# BLE_breakout.net
KiCad netlist of a schematic drawn in Altium Designer
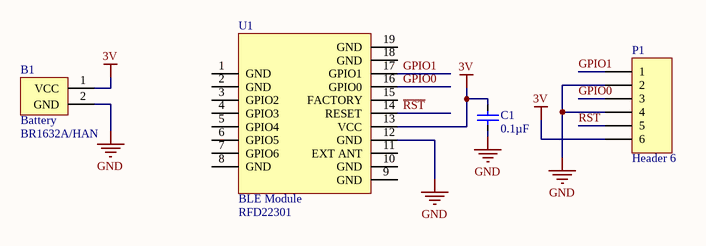
[diagram p0: BLE_breakout.SchDoc]

(export (version "E")
  (design (tool "Eeschema 10.0.6"))
  (components
    (comp (ref "B1")
      (value "Battery")
      (footprint "Battery_type1")
      (fields
        (field (name "MANUFACTURER") "Panasonic")
        (field (name "MANUFACTURER PART NUMBER") "BR1632A/HAN")
      )
      (libsource (lib "BLE_breakout") (part "Battery"))
    )
    (comp (ref "C1")
      (value "Cap 0.1µF")
      (footprint "CAPC1608N")
      (description "CAP CER 0.1UF 16V X7R 0603")
      (fields
        (field (name "MANUFACTURER") "Yageo")
        (field (name "MANUFACTURER PART NUMBER") "CC0603KRX7R7BB104")
        (field (name "CAPACITANCE") "0.1µF")
      )
      (libsource (lib "Formula_Library") (part "Cap 0.1µF"))
    )
    (comp (ref "P1")
      (value "Header 6")
      (footprint "HDR1X6")
      (description "Header, 6-Pin")
      (fields (field (name "PUBLISHER") "Altium Limited"))
      (libsource (lib "Miscellaneous Connectors") (part "Header 6"))
    )
    (comp (ref "U1")
      (value "BLE Module")
      (footprint "BLE_module")
      (fields (field (name "MANUFACTURER") "RF Digital") (field (name "MANUFACTURER PART NUMBER") "RFD22301"))
      (libsource (lib "BLE_breakout") (part "BLE Module"))
    )
  )
  (nets
    (net (code "1") (name "/GPIO0") (class "Default")
      (node (ref "P1") (pin "3") (pinfunction "3_3") (pintype "passive"))
      (node (ref "U1") (pin "16") (pinfunction "GPIO0_16") (pintype "passive"))
    )
    (net (code "2") (name "/GPIO1") (class "Default")
      (node (ref "P1") (pin "1") (pinfunction "1_1") (pintype "passive"))
      (node (ref "U1") (pin "17") (pinfunction "GPIO1_17") (pintype "passive"))
    )
    (net (code "3") (name "/~{RST}") (class "Default")
      (node (ref "P1") (pin "5") (pinfunction "5_5") (pintype "passive"))
      (node (ref "U1") (pin "14") (pinfunction "RESET_14") (pintype "passive"))
    )
    (net (code "4") (name "3V") (class "Default")
      (node (ref "B1") (pin "1") (pinfunction "VCC_1") (pintype "passive"))
      (node (ref "C1") (pin "2") (pinfunction "2_2") (pintype "passive"))
      (node (ref "P1") (pin "6") (pinfunction "6_6") (pintype "passive"))
      (node (ref "U1") (pin "13") (pinfunction "VCC_13") (pintype "passive"))
    )
    (net (code "5") (name "GND") (class "Default")
      (node (ref "B1") (pin "2") (pinfunction "GND_2") (pintype "passive"))
      (node (ref "C1") (pin "1") (pinfunction "1_1") (pintype "passive"))
      (node (ref "P1") (pin "2") (pinfunction "2_2") (pintype "passive"))
      (node (ref "P1") (pin "4") (pinfunction "4_4") (pintype "passive"))
      (node (ref "U1") (pin "12") (pinfunction "GND_12") (pintype "passive"))
    )
    (net (code "6") (name "unconnected-(U1-EXT_ANT-Pad11)") (class "Default")
      (node (ref "U1") (pin "11") (pinfunction "EXT_ANT_11") (pintype "passive"))
    )
    (net (code "7") (name "unconnected-(U1-FACTORY-Pad15)") (class "Default")
      (node (ref "U1") (pin "15") (pinfunction "FACTORY_15") (pintype "passive"))
    )
    (net (code "8") (name "unconnected-(U1-GND-Pad1)") (class "Default")
      (node (ref "U1") (pin "1") (pinfunction "GND_1") (pintype "passive"))
    )
    (net (code "9") (name "unconnected-(U1-GND-Pad2)") (class "Default")
      (node (ref "U1") (pin "2") (pinfunction "GND_2") (pintype "passive"))
    )
    (net (code "10") (name "unconnected-(U1-GND-Pad8)") (class "Default")
      (node (ref "U1") (pin "8") (pinfunction "GND_8") (pintype "passive"))
    )
    (net (code "11") (name "unconnected-(U1-GND-Pad9)") (class "Default")
      (node (ref "U1") (pin "9") (pinfunction "GND_9") (pintype "passive"))
    )
    (net (code "12") (name "unconnected-(U1-GND-Pad10)") (class "Default")
      (node (ref "U1") (pin "10") (pinfunction "GND_10") (pintype "passive"))
    )
    (net (code "13") (name "unconnected-(U1-GND-Pad18)") (class "Default")
      (node (ref "U1") (pin "18") (pinfunction "GND_18") (pintype "passive"))
    )
    (net (code "14") (name "unconnected-(U1-GND-Pad19)") (class "Default")
      (node (ref "U1") (pin "19") (pinfunction "GND_19") (pintype "passive"))
    )
    (net (code "15") (name "unconnected-(U1-GPIO2-Pad3)") (class "Default")
      (node (ref "U1") (pin "3") (pinfunction "GPIO2_3") (pintype "passive"))
    )
    (net (code "16") (name "unconnected-(U1-GPIO3-Pad4)") (class "Default")
      (node (ref "U1") (pin "4") (pinfunction "GPIO3_4") (pintype "passive"))
    )
    (net (code "17") (name "unconnected-(U1-GPIO4-Pad5)") (class "Default")
      (node (ref "U1") (pin "5") (pinfunction "GPIO4_5") (pintype "passive"))
    )
    (net (code "18") (name "unconnected-(U1-GPIO5-Pad6)") (class "Default")
      (node (ref "U1") (pin "6") (pinfunction "GPIO5_6") (pintype "passive"))
    )
    (net (code "19") (name "unconnected-(U1-GPIO6-Pad7)") (class "Default")
      (node (ref "U1") (pin "7") (pinfunction "GPIO6_7") (pintype "passive"))
    )
  )
)
